# CPU_Logic.net
KiCad netlist of a schematic drawn in Altium Designer
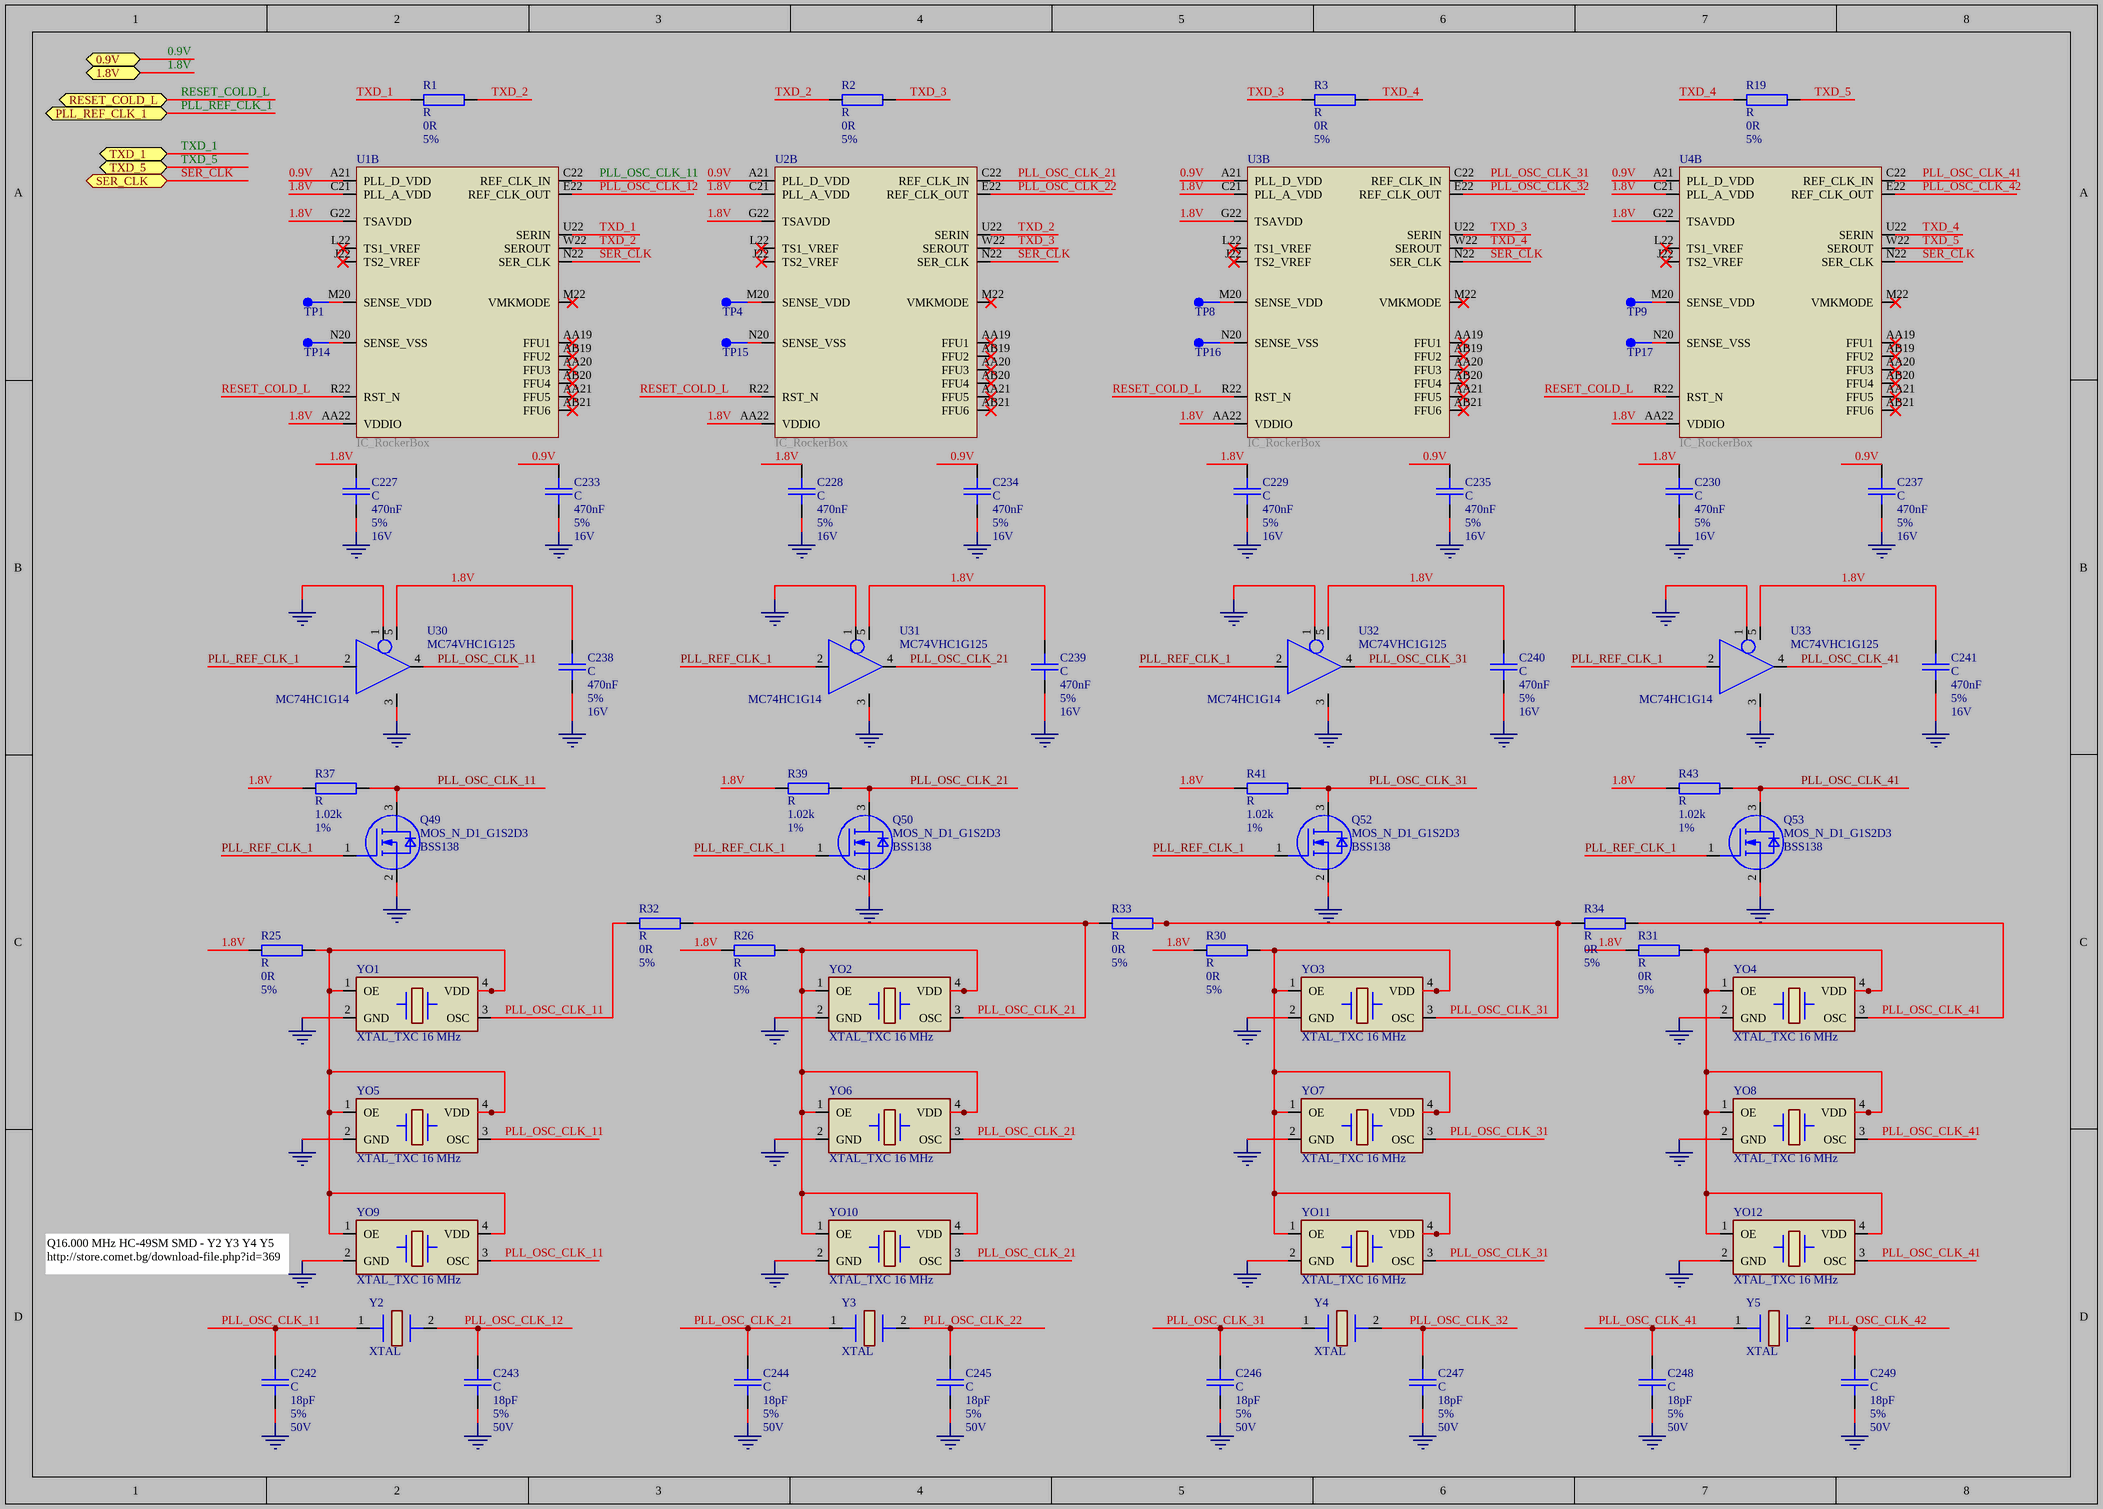
[diagram p0: CPU_Logic.SchDoc]

(export (version "E")
  (design (tool "Eeschema 10.0.6"))
  (components
    (comp (ref "C227")
      (value "C")
      (footprint "SMD_0603_CAPC1608X95N")
      (fields
        (field (name "DB_PART_NUMBER") "CAP000028169")
        (field (name "DB_VALUE") "470nF")
        (field (name "DB_TOLERANCE") "5%")
        (field (name "DB_VOLTAGE") "16V")
        (field (name "DB_MANUFACTURER_PART") "KEMET    C0603C474J4RAC")
      )
      (libsource (lib "Database_Libs1") (part "C"))
    )
    (comp (ref "C228")
      (value "C")
      (footprint "SMD_0603_CAPC1608X95N")
      (fields
        (field (name "DB_PART_NUMBER") "CAP000028169")
        (field (name "DB_VALUE") "470nF")
        (field (name "DB_TOLERANCE") "5%")
        (field (name "DB_VOLTAGE") "16V")
        (field (name "DB_MANUFACTURER_PART") "KEMET    C0603C474J4RAC")
      )
      (libsource (lib "Database_Libs1") (part "C"))
    )
    (comp (ref "C229")
      (value "C")
      (footprint "SMD_0603_CAPC1608X95N")
      (fields
        (field (name "DB_PART_NUMBER") "CAP000028169")
        (field (name "DB_VALUE") "470nF")
        (field (name "DB_TOLERANCE") "5%")
        (field (name "DB_VOLTAGE") "16V")
        (field (name "DB_MANUFACTURER_PART") "KEMET    C0603C474J4RAC")
      )
      (libsource (lib "Database_Libs1") (part "C"))
    )
    (comp (ref "C230")
      (value "C")
      (footprint "SMD_0603_CAPC1608X95N")
      (fields
        (field (name "DB_PART_NUMBER") "CAP000028169")
        (field (name "DB_VALUE") "470nF")
        (field (name "DB_TOLERANCE") "5%")
        (field (name "DB_VOLTAGE") "16V")
        (field (name "DB_MANUFACTURER_PART") "KEMET    C0603C474J4RAC")
      )
      (libsource (lib "Database_Libs1") (part "C"))
    )
    (comp (ref "C233")
      (value "C")
      (footprint "SMD_0603_CAPC1608X95N")
      (fields
        (field (name "DB_PART_NUMBER") "CAP000028169")
        (field (name "DB_VALUE") "470nF")
        (field (name "DB_TOLERANCE") "5%")
        (field (name "DB_VOLTAGE") "16V")
        (field (name "DB_MANUFACTURER_PART") "KEMET    C0603C474J4RAC")
      )
      (libsource (lib "Database_Libs1") (part "C"))
    )
    (comp (ref "C234")
      (value "C")
      (footprint "SMD_0603_CAPC1608X95N")
      (fields
        (field (name "DB_PART_NUMBER") "CAP000028169")
        (field (name "DB_VALUE") "470nF")
        (field (name "DB_TOLERANCE") "5%")
        (field (name "DB_VOLTAGE") "16V")
        (field (name "DB_MANUFACTURER_PART") "KEMET    C0603C474J4RAC")
      )
      (libsource (lib "Database_Libs1") (part "C"))
    )
    (comp (ref "C235")
      (value "C")
      (footprint "SMD_0603_CAPC1608X95N")
      (fields
        (field (name "DB_PART_NUMBER") "CAP000028169")
        (field (name "DB_VALUE") "470nF")
        (field (name "DB_TOLERANCE") "5%")
        (field (name "DB_VOLTAGE") "16V")
        (field (name "DB_MANUFACTURER_PART") "KEMET    C0603C474J4RAC")
      )
      (libsource (lib "Database_Libs1") (part "C"))
    )
    (comp (ref "C237")
      (value "C")
      (footprint "SMD_0603_CAPC1608X95N")
      (fields
        (field (name "DB_PART_NUMBER") "CAP000028169")
        (field (name "DB_VALUE") "470nF")
        (field (name "DB_TOLERANCE") "5%")
        (field (name "DB_VOLTAGE") "16V")
        (field (name "DB_MANUFACTURER_PART") "KEMET    C0603C474J4RAC")
      )
      (libsource (lib "Database_Libs1") (part "C"))
    )
    (comp (ref "C238")
      (value "C")
      (footprint "SMD_0603_CAPC1608X95N")
      (fields
        (field (name "DB_PART_NUMBER") "CAP000028169")
        (field (name "DB_VALUE") "470nF")
        (field (name "DB_TOLERANCE") "5%")
        (field (name "DB_VOLTAGE") "16V")
        (field (name "DB_MANUFACTURER_PART") "KEMET    C0603C474J4RAC")
      )
      (libsource (lib "Database_Libs1") (part "C"))
    )
    (comp (ref "C239")
      (value "C")
      (footprint "SMD_0603_CAPC1608X95N")
      (fields
        (field (name "DB_PART_NUMBER") "CAP000028169")
        (field (name "DB_VALUE") "470nF")
        (field (name "DB_TOLERANCE") "5%")
        (field (name "DB_VOLTAGE") "16V")
        (field (name "DB_MANUFACTURER_PART") "KEMET    C0603C474J4RAC")
      )
      (libsource (lib "Database_Libs1") (part "C"))
    )
    (comp (ref "C240")
      (value "C")
      (footprint "SMD_0603_CAPC1608X95N")
      (fields
        (field (name "DB_PART_NUMBER") "CAP000028169")
        (field (name "DB_VALUE") "470nF")
        (field (name "DB_TOLERANCE") "5%")
        (field (name "DB_VOLTAGE") "16V")
        (field (name "DB_MANUFACTURER_PART") "KEMET    C0603C474J4RAC")
      )
      (libsource (lib "Database_Libs1") (part "C"))
    )
    (comp (ref "C241")
      (value "C")
      (footprint "SMD_0603_CAPC1608X95N")
      (fields
        (field (name "DB_PART_NUMBER") "CAP000028169")
        (field (name "DB_VALUE") "470nF")
        (field (name "DB_TOLERANCE") "5%")
        (field (name "DB_VOLTAGE") "16V")
        (field (name "DB_MANUFACTURER_PART") "KEMET    C0603C474J4RAC")
      )
      (libsource (lib "Database_Libs1") (part "C"))
    )
    (comp (ref "C242")
      (value "C")
      (footprint "SMD_0603_CAPC1608X95N")
      (fields
        (field (name "DB_PART_NUMBER") "CAP000031922")
        (field (name "DB_VALUE") "18pF")
        (field (name "DB_TOLERANCE") "5%")
        (field (name "DB_VOLTAGE") "50V")
        (field (name "DB_MANUFACTURER_PART") "KEMET    C0603C180J5GAC")
      )
      (libsource (lib "Database_Libs1") (part "C"))
    )
    (comp (ref "C243")
      (value "C")
      (footprint "SMD_0603_CAPC1608X95N")
      (fields
        (field (name "DB_PART_NUMBER") "CAP000031922")
        (field (name "DB_VALUE") "18pF")
        (field (name "DB_TOLERANCE") "5%")
        (field (name "DB_VOLTAGE") "50V")
        (field (name "DB_MANUFACTURER_PART") "KEMET    C0603C180J5GAC")
      )
      (libsource (lib "Database_Libs1") (part "C"))
    )
    (comp (ref "C244")
      (value "C")
      (footprint "SMD_0603_CAPC1608X95N")
      (fields
        (field (name "DB_PART_NUMBER") "CAP000031922")
        (field (name "DB_VALUE") "18pF")
        (field (name "DB_TOLERANCE") "5%")
        (field (name "DB_VOLTAGE") "50V")
        (field (name "DB_MANUFACTURER_PART") "KEMET    C0603C180J5GAC")
      )
      (libsource (lib "Database_Libs1") (part "C"))
    )
    (comp (ref "C245")
      (value "C")
      (footprint "SMD_0603_CAPC1608X95N")
      (fields
        (field (name "DB_PART_NUMBER") "CAP000031922")
        (field (name "DB_VALUE") "18pF")
        (field (name "DB_TOLERANCE") "5%")
        (field (name "DB_VOLTAGE") "50V")
        (field (name "DB_MANUFACTURER_PART") "KEMET    C0603C180J5GAC")
      )
      (libsource (lib "Database_Libs1") (part "C"))
    )
    (comp (ref "C246")
      (value "C")
      (footprint "SMD_0603_CAPC1608X95N")
      (fields
        (field (name "DB_PART_NUMBER") "CAP000031922")
        (field (name "DB_VALUE") "18pF")
        (field (name "DB_TOLERANCE") "5%")
        (field (name "DB_VOLTAGE") "50V")
        (field (name "DB_MANUFACTURER_PART") "KEMET    C0603C180J5GAC")
      )
      (libsource (lib "Database_Libs1") (part "C"))
    )
    (comp (ref "C247")
      (value "C")
      (footprint "SMD_0603_CAPC1608X95N")
      (fields
        (field (name "DB_PART_NUMBER") "CAP000031922")
        (field (name "DB_VALUE") "18pF")
        (field (name "DB_TOLERANCE") "5%")
        (field (name "DB_VOLTAGE") "50V")
        (field (name "DB_MANUFACTURER_PART") "KEMET    C0603C180J5GAC")
      )
      (libsource (lib "Database_Libs1") (part "C"))
    )
    (comp (ref "C248")
      (value "C")
      (footprint "SMD_0603_CAPC1608X95N")
      (fields
        (field (name "DB_PART_NUMBER") "CAP000031922")
        (field (name "DB_VALUE") "18pF")
        (field (name "DB_TOLERANCE") "5%")
        (field (name "DB_VOLTAGE") "50V")
        (field (name "DB_MANUFACTURER_PART") "KEMET    C0603C180J5GAC")
      )
      (libsource (lib "Database_Libs1") (part "C"))
    )
    (comp (ref "C249")
      (value "C")
      (footprint "SMD_0603_CAPC1608X95N")
      (fields
        (field (name "DB_PART_NUMBER") "CAP000031922")
        (field (name "DB_VALUE") "18pF")
        (field (name "DB_TOLERANCE") "5%")
        (field (name "DB_VOLTAGE") "50V")
        (field (name "DB_MANUFACTURER_PART") "KEMET    C0603C180J5GAC")
      )
      (libsource (lib "Database_Libs1") (part "C"))
    )
    (comp (ref "Q49")
      (value "MOS_N_D1_G1S2D3")
      (footprint "SMD_SOT23_SOT95P240X112-3N")
      (fields
        (field (name "DB_PART_NUMBER") "TRA000001460")
        (field (name "DB_VALUE") "BSS138")
        (field (name "DB_MANUFACTURER_PART") "FAIRCHILD        BSS138LT1G")
        (field (name "DB_APPROVED_BY") "VSN")
      )
      (libsource (lib "Database_Libs1") (part "MOS_N_D1_G1S2D3"))
    )
    (comp (ref "Q50")
      (value "MOS_N_D1_G1S2D3")
      (footprint "SMD_SOT23_SOT95P240X112-3N")
      (fields
        (field (name "DB_PART_NUMBER") "TRA000001460")
        (field (name "DB_VALUE") "BSS138")
        (field (name "DB_MANUFACTURER_PART") "FAIRCHILD        BSS138LT1G")
        (field (name "DB_APPROVED_BY") "VSN")
      )
      (libsource (lib "Database_Libs1") (part "MOS_N_D1_G1S2D3"))
    )
    (comp (ref "Q52")
      (value "MOS_N_D1_G1S2D3")
      (footprint "SMD_SOT23_SOT95P240X112-3N")
      (fields
        (field (name "DB_PART_NUMBER") "TRA000001460")
        (field (name "DB_VALUE") "BSS138")
        (field (name "DB_MANUFACTURER_PART") "FAIRCHILD        BSS138LT1G")
        (field (name "DB_APPROVED_BY") "VSN")
      )
      (libsource (lib "Database_Libs1") (part "MOS_N_D1_G1S2D3"))
    )
    (comp (ref "Q53")
      (value "MOS_N_D1_G1S2D3")
      (footprint "SMD_SOT23_SOT95P240X112-3N")
      (fields
        (field (name "DB_PART_NUMBER") "TRA000001460")
        (field (name "DB_VALUE") "BSS138")
        (field (name "DB_MANUFACTURER_PART") "FAIRCHILD        BSS138LT1G")
        (field (name "DB_APPROVED_BY") "VSN")
      )
      (libsource (lib "Database_Libs1") (part "MOS_N_D1_G1S2D3"))
    )
    (comp (ref "R1")
      (value "R")
      (footprint "SMD_0201_RESC0603X26N")
      (fields
        (field (name "DB_PART_NUMBER") "RES000005659")
        (field (name "DB_VALUE") "0R")
        (field (name "DB_TOLERANCE") "5%")
        (field (name "DB_MANUFACTURER_PART") "YAGEO    RC0201JR-070R")
      )
      (libsource (lib "Database_Libs1") (part "R"))
    )
    (comp (ref "R2")
      (value "R")
      (footprint "SMD_0201_RESC0603X26N")
      (fields
        (field (name "DB_PART_NUMBER") "RES000005659")
        (field (name "DB_VALUE") "0R")
        (field (name "DB_TOLERANCE") "5%")
        (field (name "DB_MANUFACTURER_PART") "YAGEO    RC0201JR-070R")
      )
      (libsource (lib "Database_Libs1") (part "R"))
    )
    (comp (ref "R3")
      (value "R")
      (footprint "SMD_0201_RESC0603X26N")
      (fields
        (field (name "DB_PART_NUMBER") "RES000005659")
        (field (name "DB_VALUE") "0R")
        (field (name "DB_TOLERANCE") "5%")
        (field (name "DB_MANUFACTURER_PART") "YAGEO    RC0201JR-070R")
      )
      (libsource (lib "Database_Libs1") (part "R"))
    )
    (comp (ref "R19")
      (value "R")
      (footprint "SMD_0201_RESC0603X26N")
      (fields
        (field (name "DB_PART_NUMBER") "RES000005659")
        (field (name "DB_VALUE") "0R")
        (field (name "DB_TOLERANCE") "5%")
        (field (name "DB_MANUFACTURER_PART") "YAGEO    RC0201JR-070R")
      )
      (libsource (lib "Database_Libs1") (part "R"))
    )
    (comp (ref "R25")
      (value "R")
      (footprint "SMD_0603_RESC1608X55N")
      (fields
        (field (name "DB_PART_NUMBER") "RES000006349")
        (field (name "DB_VALUE") "0R")
        (field (name "DB_TOLERANCE") "5%")
        (field (name "DB_MANUFACTURER_PART") "YAGEO    RC0603JR-070R")
      )
      (libsource (lib "Database_Libs1") (part "R"))
    )
    (comp (ref "R26")
      (value "R")
      (footprint "SMD_0603_RESC1608X55N")
      (fields
        (field (name "DB_PART_NUMBER") "RES000006349")
        (field (name "DB_VALUE") "0R")
        (field (name "DB_TOLERANCE") "5%")
        (field (name "DB_MANUFACTURER_PART") "YAGEO    RC0603JR-070R")
      )
      (libsource (lib "Database_Libs1") (part "R"))
    )
    (comp (ref "R30")
      (value "R")
      (footprint "SMD_0603_RESC1608X55N")
      (fields
        (field (name "DB_PART_NUMBER") "RES000006349")
        (field (name "DB_VALUE") "0R")
        (field (name "DB_TOLERANCE") "5%")
        (field (name "DB_MANUFACTURER_PART") "YAGEO    RC0603JR-070R")
      )
      (libsource (lib "Database_Libs1") (part "R"))
    )
    (comp (ref "R31")
      (value "R")
      (footprint "SMD_0603_RESC1608X55N")
      (fields
        (field (name "DB_PART_NUMBER") "RES000006349")
        (field (name "DB_VALUE") "0R")
        (field (name "DB_TOLERANCE") "5%")
        (field (name "DB_MANUFACTURER_PART") "YAGEO    RC0603JR-070R")
      )
      (libsource (lib "Database_Libs1") (part "R"))
    )
    (comp (ref "R32")
      (value "R")
      (footprint "SMD_0603_RESC1608X55N")
      (fields
        (field (name "DB_PART_NUMBER") "RES000006349")
        (field (name "DB_VALUE") "0R")
        (field (name "DB_TOLERANCE") "5%")
        (field (name "DB_MANUFACTURER_PART") "YAGEO    RC0603JR-070R")
      )
      (libsource (lib "Database_Libs1") (part "R"))
    )
    (comp (ref "R33")
      (value "R")
      (footprint "SMD_0603_RESC1608X55N")
      (fields
        (field (name "DB_PART_NUMBER") "RES000006349")
        (field (name "DB_VALUE") "0R")
        (field (name "DB_TOLERANCE") "5%")
        (field (name "DB_MANUFACTURER_PART") "YAGEO    RC0603JR-070R")
      )
      (libsource (lib "Database_Libs1") (part "R"))
    )
    (comp (ref "R34")
      (value "R")
      (footprint "SMD_0603_RESC1608X55N")
      (fields
        (field (name "DB_PART_NUMBER") "RES000006349")
        (field (name "DB_VALUE") "0R")
        (field (name "DB_TOLERANCE") "5%")
        (field (name "DB_MANUFACTURER_PART") "YAGEO    RC0603JR-070R")
      )
      (libsource (lib "Database_Libs1") (part "R"))
    )
    (comp (ref "R37")
      (value "R")
      (footprint "SMD_0603_RESC1608X55N")
      (fields
        (field (name "DB_PART_NUMBER") "RES000001446")
        (field (name "DB_VALUE") "1.02k")
        (field (name "DB_TOLERANCE") "1%")
        (field (name "DB_MANUFACTURER_PART") "YAGEO    RC0603FR-071K02")
      )
      (libsource (lib "Database_Libs1") (part "R"))
    )
    (comp (ref "R39")
      (value "R")
      (footprint "SMD_0603_RESC1608X55N")
      (fields
        (field (name "DB_PART_NUMBER") "RES000001446")
        (field (name "DB_VALUE") "1.02k")
        (field (name "DB_TOLERANCE") "1%")
        (field (name "DB_MANUFACTURER_PART") "YAGEO    RC0603FR-071K02")
      )
      (libsource (lib "Database_Libs1") (part "R"))
    )
    (comp (ref "R41")
      (value "R")
      (footprint "SMD_0603_RESC1608X55N")
      (fields
        (field (name "DB_PART_NUMBER") "RES000001446")
        (field (name "DB_VALUE") "1.02k")
        (field (name "DB_TOLERANCE") "1%")
        (field (name "DB_MANUFACTURER_PART") "YAGEO    RC0603FR-071K02")
      )
      (libsource (lib "Database_Libs1") (part "R"))
    )
    (comp (ref "R43")
      (value "R")
      (footprint "SMD_0603_RESC1608X55N")
      (fields
        (field (name "DB_PART_NUMBER") "RES000001446")
        (field (name "DB_VALUE") "1.02k")
        (field (name "DB_TOLERANCE") "1%")
        (field (name "DB_MANUFACTURER_PART") "YAGEO    RC0603FR-071K02")
      )
      (libsource (lib "Database_Libs1") (part "R"))
    )
    (comp (ref "TP1")
      (value "TEST_POINT_1")
      (footprint "SMD_TP_100-254")
      (fields (field (name "DB_PART_NUMBER") "TPO000000001"))
      (libsource (lib "Database_Libs1") (part "TEST_POINT_1"))
    )
    (comp (ref "TP4")
      (value "TEST_POINT_1")
      (footprint "SMD_TP_100-254")
      (fields (field (name "DB_PART_NUMBER") "TPO000000001"))
      (libsource (lib "Database_Libs1") (part "TEST_POINT_1"))
    )
    (comp (ref "TP8")
      (value "TEST_POINT_1")
      (footprint "SMD_TP_100-254")
      (fields (field (name "DB_PART_NUMBER") "TPO000000001"))
      (libsource (lib "Database_Libs1") (part "TEST_POINT_1"))
    )
    (comp (ref "TP9")
      (value "TEST_POINT_1")
      (footprint "SMD_TP_100-254")
      (fields (field (name "DB_PART_NUMBER") "TPO000000001"))
      (libsource (lib "Database_Libs1") (part "TEST_POINT_1"))
    )
    (comp (ref "TP14")
      (value "TEST_POINT_1")
      (footprint "SMD_TP_100-254")
      (fields (field (name "DB_PART_NUMBER") "TPO000000001"))
      (libsource (lib "Database_Libs1") (part "TEST_POINT_1"))
    )
    (comp (ref "TP15")
      (value "TEST_POINT_1")
      (footprint "SMD_TP_100-254")
      (fields (field (name "DB_PART_NUMBER") "TPO000000001"))
      (libsource (lib "Database_Libs1") (part "TEST_POINT_1"))
    )
    (comp (ref "TP16")
      (value "TEST_POINT_1")
      (footprint "SMD_TP_100-254")
      (fields (field (name "DB_PART_NUMBER") "TPO000000001"))
      (libsource (lib "Database_Libs1") (part "TEST_POINT_1"))
    )
    (comp (ref "TP17")
      (value "TEST_POINT_1")
      (footprint "SMD_TP_100-254")
      (fields (field (name "DB_PART_NUMBER") "TPO000000001"))
      (libsource (lib "Database_Libs1") (part "TEST_POINT_1"))
    )
    (comp (ref "U1")
      (value "IC_RockerBox")
      (footprint "SMD_BGA480C80P22X22")
      (libsource (lib "RockerBox") (part "IC_RockerBox"))
    )
    (comp (ref "U2")
      (value "IC_RockerBox")
      (footprint "SMD_BGA480C80P22X22")
      (libsource (lib "RockerBox") (part "IC_RockerBox"))
    )
    (comp (ref "U3")
      (value "IC_RockerBox")
      (footprint "SMD_BGA480C80P22X22")
      (libsource (lib "RockerBox") (part "IC_RockerBox"))
    )
    (comp (ref "U4")
      (value "IC_RockerBox")
      (footprint "SMD_BGA480C80P22X22")
      (libsource (lib "RockerBox") (part "IC_RockerBox"))
    )
    (comp (ref "U30")
      (value "IC_BUFFER_SINGLE_5PIN_3STATE")
      (footprint "SMD_SOT95P280X110-5N")
      (fields
        (field (name "DB_PART_NUMBER") "DIG000000005")
        (field (name "DB_VALUE") "MC74VHC1G125")
        (field (name "DB_MANUFACTURER_PART") "ON Semiconductor       M74VHC1G125DTT1G")
        (field (name "DB_APPROVED_BY") "VSN")
      )
      (libsource (lib "Database_Libs1") (part "IC_BUFFER_SINGLE_5PIN_3STATE"))
    )
    (comp (ref "U31")
      (value "IC_BUFFER_SINGLE_5PIN_3STATE")
      (footprint "SMD_SOT95P280X110-5N")
      (fields
        (field (name "DB_PART_NUMBER") "DIG000000005")
        (field (name "DB_VALUE") "MC74VHC1G125")
        (field (name "DB_MANUFACTURER_PART") "ON Semiconductor       M74VHC1G125DTT1G")
        (field (name "DB_APPROVED_BY") "VSN")
      )
      (libsource (lib "Database_Libs1") (part "IC_BUFFER_SINGLE_5PIN_3STATE"))
    )
    (comp (ref "U32")
      (value "IC_BUFFER_SINGLE_5PIN_3STATE")
      (footprint "SMD_SOT95P280X110-5N")
      (fields
        (field (name "DB_PART_NUMBER") "DIG000000005")
        (field (name "DB_VALUE") "MC74VHC1G125")
        (field (name "DB_MANUFACTURER_PART") "ON Semiconductor       M74VHC1G125DTT1G")
        (field (name "DB_APPROVED_BY") "VSN")
      )
      (libsource (lib "Database_Libs1") (part "IC_BUFFER_SINGLE_5PIN_3STATE"))
    )
    (comp (ref "U33")
      (value "IC_BUFFER_SINGLE_5PIN_3STATE")
      (footprint "SMD_SOT95P280X110-5N")
      (fields
        (field (name "DB_PART_NUMBER") "DIG000000005")
        (field (name "DB_VALUE") "MC74VHC1G125")
        (field (name "DB_MANUFACTURER_PART") "ON Semiconductor       M74VHC1G125DTT1G")
        (field (name "DB_APPROVED_BY") "VSN")
      )
      (libsource (lib "Database_Libs1") (part "IC_BUFFER_SINGLE_5PIN_3STATE"))
    )
    (comp (ref "Y2")
      (value "XTAL")
      (footprint "SMD_HC49_XTAL1140X480X420N")
      (libsource (lib "RockerBox") (part "XTAL"))
    )
    (comp (ref "Y3")
      (value "XTAL")
      (footprint "SMD_HC49_XTAL1140X480X420N")
      (libsource (lib "RockerBox") (part "XTAL"))
    )
    (comp (ref "Y4")
      (value "XTAL")
      (footprint "SMD_HC49_XTAL1140X480X420N")
      (libsource (lib "RockerBox") (part "XTAL"))
    )
    (comp (ref "Y5")
      (value "XTAL")
      (footprint "SMD_HC49_XTAL1140X480X420N")
      (libsource (lib "RockerBox") (part "XTAL"))
    )
    (comp (ref "YO1")
      (value "XTAL_TXC 16 MHz")
      (footprint "SMD_OSCCF320X400X90-4N")
      (libsource (lib "RockerBox") (part "XTAL_OE1GND2OSC3VDD4"))
    )
    (comp (ref "YO2")
      (value "XTAL_TXC 16 MHz")
      (footprint "SMD_OSCCF320X400X90-4N")
      (libsource (lib "RockerBox") (part "XTAL_OE1GND2OSC3VDD4"))
    )
    (comp (ref "YO3")
      (value "XTAL_TXC 16 MHz")
      (footprint "SMD_OSCCF320X400X90-4N")
      (libsource (lib "RockerBox") (part "XTAL_OE1GND2OSC3VDD4"))
    )
    (comp (ref "YO4")
      (value "XTAL_TXC 16 MHz")
      (footprint "SMD_OSCCF320X400X90-4N")
      (libsource (lib "RockerBox") (part "XTAL_OE1GND2OSC3VDD4"))
    )
    (comp (ref "YO5")
      (value "XTAL_TXC 16 MHz")
      (footprint "SMD_OSCCF250X320X90-4N")
      (libsource (lib "RockerBox") (part "XTAL_OE1GND2OSC3VDD4"))
    )
    (comp (ref "YO6")
      (value "XTAL_TXC 16 MHz")
      (footprint "SMD_OSCCF250X320X90-4N")
      (libsource (lib "RockerBox") (part "XTAL_OE1GND2OSC3VDD4"))
    )
    (comp (ref "YO7")
      (value "XTAL_TXC 16 MHz")
      (footprint "SMD_OSCCF250X320X90-4N")
      (libsource (lib "RockerBox") (part "XTAL_OE1GND2OSC3VDD4"))
    )
    (comp (ref "YO8")
      (value "XTAL_TXC 16 MHz")
      (footprint "SMD_OSCCF250X320X90-4N")
      (libsource (lib "RockerBox") (part "XTAL_OE1GND2OSC3VDD4"))
    )
    (comp (ref "YO9")
      (value "XTAL_TXC 16 MHz")
      (footprint "SMD_OSCCF200X250X90-4N")
      (libsource (lib "RockerBox") (part "XTAL_OE1GND2OSC3VDD4"))
    )
    (comp (ref "YO10")
      (value "XTAL_TXC 16 MHz")
      (footprint "SMD_OSCCF200X250X90-4N")
      (libsource (lib "RockerBox") (part "XTAL_OE1GND2OSC3VDD4"))
    )
    (comp (ref "YO11")
      (value "XTAL_TXC 16 MHz")
      (footprint "SMD_OSCCF200X250X90-4N")
      (libsource (lib "RockerBox") (part "XTAL_OE1GND2OSC3VDD4"))
    )
    (comp (ref "YO12")
      (value "XTAL_TXC 16 MHz")
      (footprint "SMD_OSCCF200X250X90-4N")
      (libsource (lib "RockerBox") (part "XTAL_OE1GND2OSC3VDD4"))
    )
  )
  (nets
    (net (code "1") (name "/0.9V") (class "Default")
      (node (ref "C233") (pin "2") (pinfunction "2_2") (pintype "passive"))
      (node (ref "C234") (pin "2") (pinfunction "2_2") (pintype "passive"))
      (node (ref "C235") (pin "2") (pinfunction "2_2") (pintype "passive"))
      (node (ref "C237") (pin "2") (pinfunction "2_2") (pintype "passive"))
      (node (ref "U1") (pin "A21") (pinfunction "PLL_D_VDD_A21") (pintype "passive"))
      (node (ref "U2") (pin "A21") (pinfunction "PLL_D_VDD_A21") (pintype "passive"))
      (node (ref "U3") (pin "A21") (pinfunction "PLL_D_VDD_A21") (pintype "passive"))
      (node (ref "U4") (pin "A21") (pinfunction "PLL_D_VDD_A21") (pintype "passive"))
    )
    (net (code "2") (name "/1.8V") (class "Default")
      (node (ref "C227") (pin "2") (pinfunction "2_2") (pintype "passive"))
      (node (ref "C228") (pin "2") (pinfunction "2_2") (pintype "passive"))
      (node (ref "C229") (pin "2") (pinfunction "2_2") (pintype "passive"))
      (node (ref "C230") (pin "2") (pinfunction "2_2") (pintype "passive"))
      (node (ref "C238") (pin "2") (pinfunction "2_2") (pintype "passive"))
      (node (ref "C239") (pin "2") (pinfunction "2_2") (pintype "passive"))
      (node (ref "C240") (pin "2") (pinfunction "2_2") (pintype "passive"))
      (node (ref "C241") (pin "2") (pinfunction "2_2") (pintype "passive"))
      (node (ref "R25") (pin "1") (pinfunction "1_1") (pintype "passive"))
      (node (ref "R26") (pin "1") (pinfunction "1_1") (pintype "passive"))
      (node (ref "R30") (pin "1") (pinfunction "1_1") (pintype "passive"))
      (node (ref "R31") (pin "1") (pinfunction "1_1") (pintype "passive"))
      (node (ref "R37") (pin "1") (pinfunction "1_1") (pintype "passive"))
      (node (ref "R39") (pin "1") (pinfunction "1_1") (pintype "passive"))
      (node (ref "R41") (pin "1") (pinfunction "1_1") (pintype "passive"))
      (node (ref "R43") (pin "1") (pinfunction "1_1") (pintype "passive"))
      (node (ref "U1") (pin "AA22") (pinfunction "VDDIO_AA22") (pintype "passive"))
      (node (ref "U1") (pin "C21") (pinfunction "PLL_A_VDD_C21") (pintype "passive"))
      (node (ref "U1") (pin "G22") (pinfunction "TSAVDD_G22") (pintype "passive"))
      (node (ref "U2") (pin "AA22") (pinfunction "VDDIO_AA22") (pintype "passive"))
      (node (ref "U2") (pin "C21") (pinfunction "PLL_A_VDD_C21") (pintype "passive"))
      (node (ref "U2") (pin "G22") (pinfunction "TSAVDD_G22") (pintype "passive"))
      (node (ref "U3") (pin "AA22") (pinfunction "VDDIO_AA22") (pintype "passive"))
      (node (ref "U3") (pin "C21") (pinfunction "PLL_A_VDD_C21") (pintype "passive"))
      (node (ref "U3") (pin "G22") (pinfunction "TSAVDD_G22") (pintype "passive"))
      (node (ref "U30") (pin "5") (pinfunction "VCC_5") (pintype "passive"))
      (node (ref "U31") (pin "5") (pinfunction "VCC_5") (pintype "passive"))
      (node (ref "U32") (pin "5") (pinfunction "VCC_5") (pintype "passive"))
      (node (ref "U33") (pin "5") (pinfunction "VCC_5") (pintype "passive"))
      (node (ref "U4") (pin "AA22") (pinfunction "VDDIO_AA22") (pintype "passive"))
      (node (ref "U4") (pin "C21") (pinfunction "PLL_A_VDD_C21") (pintype "passive"))
      (node (ref "U4") (pin "G22") (pinfunction "TSAVDD_G22") (pintype "passive"))
    )
    (net (code "3") (name "/PLL_OSC_CLK_11") (class "Default")
      (node (ref "C242") (pin "1") (pinfunction "1_1") (pintype "passive"))
      (node (ref "Q49") (pin "3") (pinfunction "D_3") (pintype "passive"))
      (node (ref "R32") (pin "1") (pinfunction "1_1") (pintype "passive"))
      (node (ref "R37") (pin "2") (pinfunction "2_2") (pintype "passive"))
      (node (ref "U1") (pin "C22") (pinfunction "REF_CLK_IN_C22") (pintype "passive"))
      (node (ref "U30") (pin "4") (pinfunction "OUTY_4") (pintype "passive"))
      (node (ref "Y2") (pin "1") (pinfunction "1_1") (pintype "passive"))
      (node (ref "YO1") (pin "3") (pinfunction "OSC_3") (pintype "passive"))
      (node (ref "YO5") (pin "3") (pinfunction "OSC_3") (pintype "passive"))
      (node (ref "YO9") (pin "3") (pinfunction "OSC_3") (pintype "passive"))
    )
    (net (code "4") (name "/PLL_OSC_CLK_12") (class "Default")
      (node (ref "C243") (pin "1") (pinfunction "1_1") (pintype "passive"))
      (node (ref "U1") (pin "E22") (pinfunction "REF_CLK_OUT_E22") (pintype "passive"))
      (node (ref "Y2") (pin "2") (pinfunction "2_2") (pintype "passive"))
    )
    (net (code "5") (name "/PLL_OSC_CLK_21") (class "Default")
      (node (ref "C244") (pin "1") (pinfunction "1_1") (pintype "passive"))
      (node (ref "Q50") (pin "3") (pinfunction "D_3") (pintype "passive"))
      (node (ref "R32") (pin "2") (pinfunction "2_2") (pintype "passive"))
      (node (ref "R33") (pin "1") (pinfunction "1_1") (pintype "passive"))
      (node (ref "R39") (pin "2") (pinfunction "2_2") (pintype "passive"))
      (node (ref "U2") (pin "C22") (pinfunction "REF_CLK_IN_C22") (pintype "passive"))
      (node (ref "U31") (pin "4") (pinfunction "OUTY_4") (pintype "passive"))
      (node (ref "Y3") (pin "1") (pinfunction "1_1") (pintype "passive"))
      (node (ref "YO10") (pin "3") (pinfunction "OSC_3") (pintype "passive"))
      (node (ref "YO2") (pin "3") (pinfunction "OSC_3") (pintype "passive"))
      (node (ref "YO6") (pin "3") (pinfunction "OSC_3") (pintype "passive"))
    )
    (net (code "6") (name "/PLL_OSC_CLK_22") (class "Default")
      (node (ref "C245") (pin "1") (pinfunction "1_1") (pintype "passive"))
      (node (ref "U2") (pin "E22") (pinfunction "REF_CLK_OUT_E22") (pintype "passive"))
      (node (ref "Y3") (pin "2") (pinfunction "2_2") (pintype "passive"))
    )
    (net (code "7") (name "/PLL_OSC_CLK_31") (class "Default")
      (node (ref "C246") (pin "1") (pinfunction "1_1") (pintype "passive"))
      (node (ref "Q52") (pin "3") (pinfunction "D_3") (pintype "passive"))
      (node (ref "R33") (pin "2") (pinfunction "2_2") (pintype "passive"))
      (node (ref "R34") (pin "1") (pinfunction "1_1") (pintype "passive"))
      (node (ref "R41") (pin "2") (pinfunction "2_2") (pintype "passive"))
      (node (ref "U3") (pin "C22") (pinfunction "REF_CLK_IN_C22") (pintype "passive"))
      (node (ref "U32") (pin "4") (pinfunction "OUTY_4") (pintype "passive"))
      (node (ref "Y4") (pin "1") (pinfunction "1_1") (pintype "passive"))
      (node (ref "YO11") (pin "3") (pinfunction "OSC_3") (pintype "passive"))
      (node (ref "YO3") (pin "3") (pinfunction "OSC_3") (pintype "passive"))
      (node (ref "YO7") (pin "3") (pinfunction "OSC_3") (pintype "passive"))
    )
    (net (code "8") (name "/PLL_OSC_CLK_32") (class "Default")
      (node (ref "C247") (pin "1") (pinfunction "1_1") (pintype "passive"))
      (node (ref "U3") (pin "E22") (pinfunction "REF_CLK_OUT_E22") (pintype "passive"))
      (node (ref "Y4") (pin "2") (pinfunction "2_2") (pintype "passive"))
    )
    (net (code "9") (name "/PLL_OSC_CLK_41") (class "Default")
      (node (ref "C248") (pin "1") (pinfunction "1_1") (pintype "passive"))
      (node (ref "Q53") (pin "3") (pinfunction "D_3") (pintype "passive"))
      (node (ref "R34") (pin "2") (pinfunction "2_2") (pintype "passive"))
      (node (ref "R43") (pin "2") (pinfunction "2_2") (pintype "passive"))
      (node (ref "U33") (pin "4") (pinfunction "OUTY_4") (pintype "passive"))
      (node (ref "U4") (pin "C22") (pinfunction "REF_CLK_IN_C22") (pintype "passive"))
      (node (ref "Y5") (pin "1") (pinfunction "1_1") (pintype "passive"))
      (node (ref "YO12") (pin "3") (pinfunction "OSC_3") (pintype "passive"))
      (node (ref "YO4") (pin "3") (pinfunction "OSC_3") (pintype "passive"))
      (node (ref "YO8") (pin "3") (pinfunction "OSC_3") (pintype "passive"))
    )
    (net (code "10") (name "/PLL_OSC_CLK_42") (class "Default")
      (node (ref "C249") (pin "1") (pinfunction "1_1") (pintype "passive"))
      (node (ref "U4") (pin "E22") (pinfunction "REF_CLK_OUT_E22") (pintype "passive"))
      (node (ref "Y5") (pin "2") (pinfunction "2_2") (pintype "passive"))
    )
    (net (code "11") (name "/PLL_REF_CLK_1") (class "Default")
      (node (ref "Q49") (pin "1") (pinfunction "G_1") (pintype "passive"))
      (node (ref "Q50") (pin "1") (pinfunction "G_1") (pintype "passive"))
      (node (ref "Q52") (pin "1") (pinfunction "G_1") (pintype "passive"))
      (node (ref "Q53") (pin "1") (pinfunction "G_1") (pintype "passive"))
      (node (ref "U30") (pin "2") (pinfunction "INA_2") (pintype "passive"))
      (node (ref "U31") (pin "2") (pinfunction "INA_2") (pintype "passive"))
      (node (ref "U32") (pin "2") (pinfunction "INA_2") (pintype "passive"))
      (node (ref "U33") (pin "2") (pinfunction "INA_2") (pintype "passive"))
    )
    (net (code "12") (name "/RESET_COLD_L") (class "Default")
      (node (ref "U1") (pin "R22") (pinfunction "RST_N_R22") (pintype "passive"))
      (node (ref "U2") (pin "R22") (pinfunction "RST_N_R22") (pintype "passive"))
      (node (ref "U3") (pin "R22") (pinfunction "RST_N_R22") (pintype "passive"))
      (node (ref "U4") (pin "R22") (pinfunction "RST_N_R22") (pintype "passive"))
    )
    (net (code "13") (name "/SER_CLK") (class "Default")
      (node (ref "U1") (pin "N22") (pinfunction "SER_CLK_N22") (pintype "passive"))
      (node (ref "U2") (pin "N22") (pinfunction "SER_CLK_N22") (pintype "passive"))
      (node (ref "U3") (pin "N22") (pinfunction "SER_CLK_N22") (pintype "passive"))
      (node (ref "U4") (pin "N22") (pinfunction "SER_CLK_N22") (pintype "passive"))
    )
    (net (code "14") (name "/TXD_1") (class "Default")
      (node (ref "R1") (pin "1") (pinfunction "1_1") (pintype "passive"))
      (node (ref "U1") (pin "U22") (pinfunction "SERIN_U22") (pintype "passive"))
    )
    (net (code "15") (name "/TXD_2") (class "Default")
      (node (ref "R1") (pin "2") (pinfunction "2_2") (pintype "passive"))
      (node (ref "R2") (pin "1") (pinfunction "1_1") (pintype "passive"))
      (node (ref "U1") (pin "W22") (pinfunction "SEROUT_W22") (pintype "passive"))
      (node (ref "U2") (pin "U22") (pinfunction "SERIN_U22") (pintype "passive"))
    )
    (net (code "16") (name "/TXD_3") (class "Default")
      (node (ref "R2") (pin "2") (pinfunction "2_2") (pintype "passive"))
      (node (ref "R3") (pin "1") (pinfunction "1_1") (pintype "passive"))
      (node (ref "U2") (pin "W22") (pinfunction "SEROUT_W22") (pintype "passive"))
      (node (ref "U3") (pin "U22") (pinfunction "SERIN_U22") (pintype "passive"))
    )
    (net (code "17") (name "/TXD_4") (class "Default")
      (node (ref "R19") (pin "1") (pinfunction "1_1") (pintype "passive"))
      (node (ref "R3") (pin "2") (pinfunction "2_2") (pintype "passive"))
      (node (ref "U3") (pin "W22") (pinfunction "SEROUT_W22") (pintype "passive"))
      (node (ref "U4") (pin "U22") (pinfunction "SERIN_U22") (pintype "passive"))
    )
    (net (code "18") (name "/TXD_5") (class "Default")
      (node (ref "R19") (pin "2") (pinfunction "2_2") (pintype "passive"))
      (node (ref "U4") (pin "W22") (pinfunction "SEROUT_W22") (pintype "passive"))
    )
    (net (code "19") (name "GND") (class "Default")
      (node (ref "C227") (pin "1") (pinfunction "1_1") (pintype "passive"))
      (node (ref "C228") (pin "1") (pinfunction "1_1") (pintype "passive"))
      (node (ref "C229") (pin "1") (pinfunction "1_1") (pintype "passive"))
      (node (ref "C230") (pin "1") (pinfunction "1_1") (pintype "passive"))
      (node (ref "C233") (pin "1") (pinfunction "1_1") (pintype "passive"))
      (node (ref "C234") (pin "1") (pinfunction "1_1") (pintype "passive"))
      (node (ref "C235") (pin "1") (pinfunction "1_1") (pintype "passive"))
      (node (ref "C237") (pin "1") (pinfunction "1_1") (pintype "passive"))
      (node (ref "C238") (pin "1") (pinfunction "1_1") (pintype "passive"))
      (node (ref "C239") (pin "1") (pinfunction "1_1") (pintype "passive"))
      (node (ref "C240") (pin "1") (pinfunction "1_1") (pintype "passive"))
      (node (ref "C241") (pin "1") (pinfunction "1_1") (pintype "passive"))
      (node (ref "C242") (pin "2") (pinfunction "2_2") (pintype "passive"))
      (node (ref "C243") (pin "2") (pinfunction "2_2") (pintype "passive"))
      (node (ref "C244") (pin "2") (pinfunction "2_2") (pintype "passive"))
      (node (ref "C245") (pin "2") (pinfunction "2_2") (pintype "passive"))
      (node (ref "C246") (pin "2") (pinfunction "2_2") (pintype "passive"))
      (node (ref "C247") (pin "2") (pinfunction "2_2") (pintype "passive"))
      (node (ref "C248") (pin "2") (pinfunction "2_2") (pintype "passive"))
      (node (ref "C249") (pin "2") (pinfunction "2_2") (pintype "passive"))
      (node (ref "Q49") (pin "2") (pinfunction "S_2") (pintype "passive"))
      (node (ref "Q50") (pin "2") (pinfunction "S_2") (pintype "passive"))
      (node (ref "Q52") (pin "2") (pinfunction "S_2") (pintype "passive"))
      (node (ref "Q53") (pin "2") (pinfunction "S_2") (pintype "passive"))
      (node (ref "U30") (pin "1") (pinfunction "~{OE}_1") (pintype "passive"))
      (node (ref "U30") (pin "3") (pinfunction "GND_3") (pintype "passive"))
      (node (ref "U31") (pin "1") (pinfunction "~{OE}_1") (pintype "passive"))
      (node (ref "U31") (pin "3") (pinfunction "GND_3") (pintype "passive"))
      (node (ref "U32") (pin "1") (pinfunction "~{OE}_1") (pintype "passive"))
      (node (ref "U32") (pin "3") (pinfunction "GND_3") (pintype "passive"))
      (node (ref "U33") (pin "1") (pinfunction "~{OE}_1") (pintype "passive"))
      (node (ref "U33") (pin "3") (pinfunction "GND_3") (pintype "passive"))
      (node (ref "YO1") (pin "2") (pinfunction "GND_2") (pintype "passive"))
      (node (ref "YO10") (pin "2") (pinfunction "GND_2") (pintype "passive"))
      (node (ref "YO11") (pin "2") (pinfunction "GND_2") (pintype "passive"))
      (node (ref "YO12") (pin "2") (pinfunction "GND_2") (pintype "passive"))
      (node (ref "YO2") (pin "2") (pinfunction "GND_2") (pintype "passive"))
      (node (ref "YO3") (pin "2") (pinfunction "GND_2") (pintype "passive"))
      (node (ref "YO4") (pin "2") (pinfunction "GND_2") (pintype "passive"))
      (node (ref "YO5") (pin "2") (pinfunction "GND_2") (pintype "passive"))
      (node (ref "YO6") (pin "2") (pinfunction "GND_2") (pintype "passive"))
      (node (ref "YO7") (pin "2") (pinfunction "GND_2") (pintype "passive"))
      (node (ref "YO8") (pin "2") (pinfunction "GND_2") (pintype "passive"))
      (node (ref "YO9") (pin "2") (pinfunction "GND_2") (pintype "passive"))
    )
    (net (code "20") (name "Net-(U1B-SENSE_VDD)") (class "Default")
      (node (ref "TP1") (pin "1") (pinfunction "1_1") (pintype "passive"))
      (node (ref "U1") (pin "M20") (pinfunction "SENSE_VDD_M20") (pintype "passive"))
    )
    (net (code "21") (name "Net-(U1B-SENSE_VSS)") (class "Default")
      (node (ref "TP14") (pin "1") (pinfunction "1_1") (pintype "passive"))
      (node (ref "U1") (pin "N20") (pinfunction "SENSE_VSS_N20") (pintype "passive"))
    )
    (net (code "22") (name "Net-(U2B-SENSE_VDD)") (class "Default")
      (node (ref "TP4") (pin "1") (pinfunction "1_1") (pintype "passive"))
      (node (ref "U2") (pin "M20") (pinfunction "SENSE_VDD_M20") (pintype "passive"))
    )
    (net (code "23") (name "Net-(U2B-SENSE_VSS)") (class "Default")
      (node (ref "TP15") (pin "1") (pinfunction "1_1") (pintype "passive"))
      (node (ref "U2") (pin "N20") (pinfunction "SENSE_VSS_N20") (pintype "passive"))
    )
    (net (code "24") (name "Net-(U3B-SENSE_VDD)") (class "Default")
      (node (ref "TP8") (pin "1") (pinfunction "1_1") (pintype "passive"))
      (node (ref "U3") (pin "M20") (pinfunction "SENSE_VDD_M20") (pintype "passive"))
    )
    (net (code "25") (name "Net-(U3B-SENSE_VSS)") (class "Default")
      (node (ref "TP16") (pin "1") (pinfunction "1_1") (pintype "passive"))
      (node (ref "U3") (pin "N20") (pinfunction "SENSE_VSS_N20") (pintype "passive"))
    )
    (net (code "26") (name "Net-(U4B-SENSE_VDD)") (class "Default")
      (node (ref "TP9") (pin "1") (pinfunction "1_1") (pintype "passive"))
      (node (ref "U4") (pin "M20") (pinfunction "SENSE_VDD_M20") (pintype "passive"))
    )
    (net (code "27") (name "Net-(U4B-SENSE_VSS)") (class "Default")
      (node (ref "TP17") (pin "1") (pinfunction "1_1") (pintype "passive"))
      (node (ref "U4") (pin "N20") (pinfunction "SENSE_VSS_N20") (pintype "passive"))
    )
    (net (code "28") (name "Net-(YO1-OE)") (class "Default")
      (node (ref "R25") (pin "2") (pinfunction "2_2") (pintype "passive"))
      (node (ref "YO1") (pin "1") (pinfunction "OE_1") (pintype "passive"))
      (node (ref "YO1") (pin "4") (pinfunction "VDD_4") (pintype "passive"))
      (node (ref "YO5") (pin "1") (pinfunction "OE_1") (pintype "passive"))
      (node (ref "YO5") (pin "4") (pinfunction "VDD_4") (pintype "passive"))
      (node (ref "YO9") (pin "1") (pinfunction "OE_1") (pintype "passive"))
      (node (ref "YO9") (pin "4") (pinfunction "VDD_4") (pintype "passive"))
    )
    (net (code "29") (name "Net-(YO10-OE)") (class "Default")
      (node (ref "R26") (pin "2") (pinfunction "2_2") (pintype "passive"))
      (node (ref "YO10") (pin "1") (pinfunction "OE_1") (pintype "passive"))
      (node (ref "YO10") (pin "4") (pinfunction "VDD_4") (pintype "passive"))
      (node (ref "YO2") (pin "1") (pinfunction "OE_1") (pintype "passive"))
      (node (ref "YO2") (pin "4") (pinfunction "VDD_4") (pintype "passive"))
      (node (ref "YO6") (pin "1") (pinfunction "OE_1") (pintype "passive"))
      (node (ref "YO6") (pin "4") (pinfunction "VDD_4") (pintype "passive"))
    )
    (net (code "30") (name "Net-(YO11-OE)") (class "Default")
      (node (ref "R30") (pin "2") (pinfunction "2_2") (pintype "passive"))
      (node (ref "YO11") (pin "1") (pinfunction "OE_1") (pintype "passive"))
      (node (ref "YO11") (pin "4") (pinfunction "VDD_4") (pintype "passive"))
      (node (ref "YO3") (pin "1") (pinfunction "OE_1") (pintype "passive"))
      (node (ref "YO3") (pin "4") (pinfunction "VDD_4") (pintype "passive"))
      (node (ref "YO7") (pin "1") (pinfunction "OE_1") (pintype "passive"))
      (node (ref "YO7") (pin "4") (pinfunction "VDD_4") (pintype "passive"))
    )
    (net (code "31") (name "Net-(YO12-OE)") (class "Default")
      (node (ref "R31") (pin "2") (pinfunction "2_2") (pintype "passive"))
      (node (ref "YO12") (pin "1") (pinfunction "OE_1") (pintype "passive"))
      (node (ref "YO12") (pin "4") (pinfunction "VDD_4") (pintype "passive"))
      (node (ref "YO4") (pin "1") (pinfunction "OE_1") (pintype "passive"))
      (node (ref "YO4") (pin "4") (pinfunction "VDD_4") (pintype "passive"))
      (node (ref "YO8") (pin "1") (pinfunction "OE_1") (pintype "passive"))
      (node (ref "YO8") (pin "4") (pinfunction "VDD_4") (pintype "passive"))
    )
    (net (code "32") (name "unconnected-(U1B-FFU1-PadAA19)") (class "Default")
      (node (ref "U1") (pin "AA19") (pinfunction "FFU1_AA19") (pintype "passive+no_connect"))
    )
    (net (code "33") (name "unconnected-(U1B-FFU2-PadAB19)") (class "Default")
      (node (ref "U1") (pin "AB19") (pinfunction "FFU2_AB19") (pintype "passive+no_connect"))
    )
    (net (code "34") (name "unconnected-(U1B-FFU3-PadAA20)") (class "Default")
      (node (ref "U1") (pin "AA20") (pinfunction "FFU3_AA20") (pintype "passive+no_connect"))
    )
    (net (code "35") (name "unconnected-(U1B-FFU4-PadAB20)") (class "Default")
      (node (ref "U1") (pin "AB20") (pinfunction "FFU4_AB20") (pintype "passive+no_connect"))
    )
    (net (code "36") (name "unconnected-(U1B-FFU5-PadAA21)") (class "Default")
      (node (ref "U1") (pin "AA21") (pinfunction "FFU5_AA21") (pintype "passive+no_connect"))
    )
    (net (code "37") (name "unconnected-(U1B-FFU6-PadAB21)") (class "Default")
      (node (ref "U1") (pin "AB21") (pinfunction "FFU6_AB21") (pintype "passive+no_connect"))
    )
    (net (code "38") (name "unconnected-(U1B-TS1_VREF-PadL22)") (class "Default")
      (node (ref "U1") (pin "L22") (pinfunction "TS1_VREF_L22") (pintype "passive+no_connect"))
    )
    (net (code "39") (name "unconnected-(U1B-TS2_VREF-PadJ22)") (class "Default")
      (node (ref "U1") (pin "J22") (pinfunction "TS2_VREF_J22") (pintype "passive+no_connect"))
    )
    (net (code "40") (name "unconnected-(U1B-VMKMODE-PadM22)") (class "Default")
      (node (ref "U1") (pin "M22") (pinfunction "VMKMODE_M22") (pintype "passive+no_connect"))
    )
    (net (code "41") (name "unconnected-(U2B-FFU1-PadAA19)") (class "Default")
      (node (ref "U2") (pin "AA19") (pinfunction "FFU1_AA19") (pintype "passive+no_connect"))
    )
    (net (code "42") (name "unconnected-(U2B-FFU2-PadAB19)") (class "Default")
      (node (ref "U2") (pin "AB19") (pinfunction "FFU2_AB19") (pintype "passive+no_connect"))
    )
    (net (code "43") (name "unconnected-(U2B-FFU3-PadAA20)") (class "Default")
      (node (ref "U2") (pin "AA20") (pinfunction "FFU3_AA20") (pintype "passive+no_connect"))
    )
    (net (code "44") (name "unconnected-(U2B-FFU4-PadAB20)") (class "Default")
      (node (ref "U2") (pin "AB20") (pinfunction "FFU4_AB20") (pintype "passive+no_connect"))
    )
    (net (code "45") (name "unconnected-(U2B-FFU5-PadAA21)") (class "Default")
      (node (ref "U2") (pin "AA21") (pinfunction "FFU5_AA21") (pintype "passive+no_connect"))
    )
    (net (code "46") (name "unconnected-(U2B-FFU6-PadAB21)") (class "Default")
      (node (ref "U2") (pin "AB21") (pinfunction "FFU6_AB21") (pintype "passive+no_connect"))
    )
    (net (code "47") (name "unconnected-(U2B-TS1_VREF-PadL22)") (class "Default")
      (node (ref "U2") (pin "L22") (pinfunction "TS1_VREF_L22") (pintype "passive+no_connect"))
    )
    (net (code "48") (name "unconnected-(U2B-TS2_VREF-PadJ22)") (class "Default")
      (node (ref "U2") (pin "J22") (pinfunction "TS2_VREF_J22") (pintype "passive+no_connect"))
    )
    (net (code "49") (name "unconnected-(U2B-VMKMODE-PadM22)") (class "Default")
      (node (ref "U2") (pin "M22") (pinfunction "VMKMODE_M22") (pintype "passive+no_connect"))
    )
    (net (code "50") (name "unconnected-(U3B-FFU1-PadAA19)") (class "Default")
      (node (ref "U3") (pin "AA19") (pinfunction "FFU1_AA19") (pintype "passive+no_connect"))
    )
    (net (code "51") (name "unconnected-(U3B-FFU2-PadAB19)") (class "Default")
      (node (ref "U3") (pin "AB19") (pinfunction "FFU2_AB19") (pintype "passive+no_connect"))
    )
    (net (code "52") (name "unconnected-(U3B-FFU3-PadAA20)") (class "Default")
      (node (ref "U3") (pin "AA20") (pinfunction "FFU3_AA20") (pintype "passive+no_connect"))
    )
    (net (code "53") (name "unconnected-(U3B-FFU4-PadAB20)") (class "Default")
      (node (ref "U3") (pin "AB20") (pinfunction "FFU4_AB20") (pintype "passive+no_connect"))
    )
    (net (code "54") (name "unconnected-(U3B-FFU5-PadAA21)") (class "Default")
      (node (ref "U3") (pin "AA21") (pinfunction "FFU5_AA21") (pintype "passive+no_connect"))
    )
    (net (code "55") (name "unconnected-(U3B-FFU6-PadAB21)") (class "Default")
      (node (ref "U3") (pin "AB21") (pinfunction "FFU6_AB21") (pintype "passive+no_connect"))
    )
    (net (code "56") (name "unconnected-(U3B-TS1_VREF-PadL22)") (class "Default")
      (node (ref "U3") (pin "L22") (pinfunction "TS1_VREF_L22") (pintype "passive+no_connect"))
    )
    (net (code "57") (name "unconnected-(U3B-TS2_VREF-PadJ22)") (class "Default")
      (node (ref "U3") (pin "J22") (pinfunction "TS2_VREF_J22") (pintype "passive+no_connect"))
    )
    (net (code "58") (name "unconnected-(U3B-VMKMODE-PadM22)") (class "Default")
      (node (ref "U3") (pin "M22") (pinfunction "VMKMODE_M22") (pintype "passive+no_connect"))
    )
    (net (code "59") (name "unconnected-(U4B-FFU1-PadAA19)") (class "Default")
      (node (ref "U4") (pin "AA19") (pinfunction "FFU1_AA19") (pintype "passive+no_connect"))
    )
    (net (code "60") (name "unconnected-(U4B-FFU2-PadAB19)") (class "Default")
      (node (ref "U4") (pin "AB19") (pinfunction "FFU2_AB19") (pintype "passive+no_connect"))
    )
    (net (code "61") (name "unconnected-(U4B-FFU3-PadAA20)") (class "Default")
      (node (ref "U4") (pin "AA20") (pinfunction "FFU3_AA20") (pintype "passive+no_connect"))
    )
    (net (code "62") (name "unconnected-(U4B-FFU4-PadAB20)") (class "Default")
      (node (ref "U4") (pin "AB20") (pinfunction "FFU4_AB20") (pintype "passive+no_connect"))
    )
    (net (code "63") (name "unconnected-(U4B-FFU5-PadAA21)") (class "Default")
      (node (ref "U4") (pin "AA21") (pinfunction "FFU5_AA21") (pintype "passive+no_connect"))
    )
    (net (code "64") (name "unconnected-(U4B-FFU6-PadAB21)") (class "Default")
      (node (ref "U4") (pin "AB21") (pinfunction "FFU6_AB21") (pintype "passive+no_connect"))
    )
    (net (code "65") (name "unconnected-(U4B-TS1_VREF-PadL22)") (class "Default")
      (node (ref "U4") (pin "L22") (pinfunction "TS1_VREF_L22") (pintype "passive+no_connect"))
    )
    (net (code "66") (name "unconnected-(U4B-TS2_VREF-PadJ22)") (class "Default")
      (node (ref "U4") (pin "J22") (pinfunction "TS2_VREF_J22") (pintype "passive+no_connect"))
    )
    (net (code "67") (name "unconnected-(U4B-VMKMODE-PadM22)") (class "Default")
      (node (ref "U4") (pin "M22") (pinfunction "VMKMODE_M22") (pintype "passive+no_connect"))
    )
  )
)
